# max7219.net
KiCad netlist of a schematic drawn in EAGLE
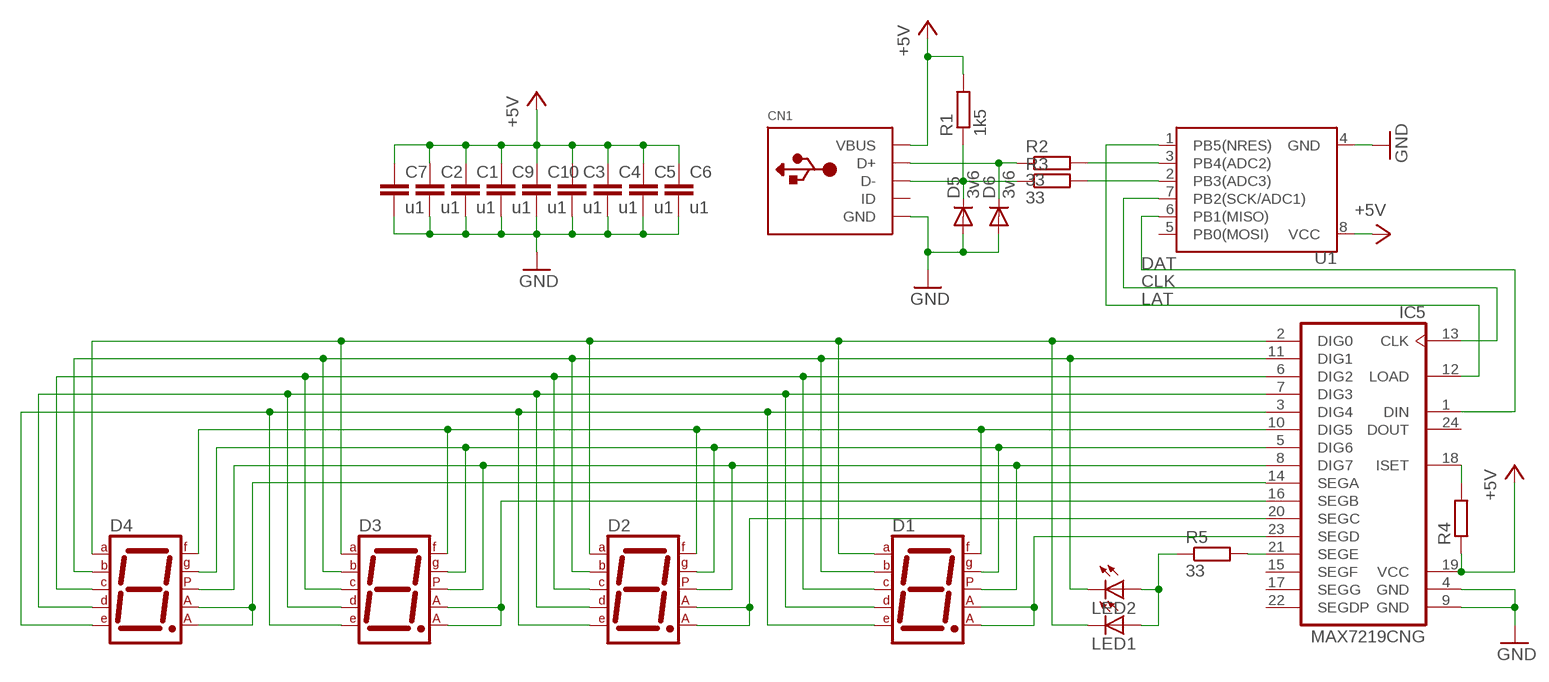
[diagram p0: schematic, sheet 1]

(export (version "E")
  (design (tool "Eeschema 10.0.6"))
  (components
    (comp (ref "C1")
      (value "u1")
      (footprint "eagle-import:C0805K")
      (libsource (lib "eagle-import") (part "C-EUC0805K"))
    )
    (comp (ref "C2")
      (value "u1")
      (footprint "eagle-import:C0805K")
      (libsource (lib "eagle-import") (part "C-EUC0805K"))
    )
    (comp (ref "C3")
      (value "u1")
      (footprint "eagle-import:C0805K")
      (libsource (lib "eagle-import") (part "C-EUC0805K"))
    )
    (comp (ref "C4")
      (value "u1")
      (footprint "eagle-import:C0805K")
      (libsource (lib "eagle-import") (part "C-EUC0805K"))
    )
    (comp (ref "C5")
      (value "u1")
      (footprint "eagle-import:C0805K")
      (libsource (lib "eagle-import") (part "C-EUC0805K"))
    )
    (comp (ref "C6")
      (value "u1")
      (footprint "eagle-import:C0805K")
      (libsource (lib "eagle-import") (part "C-EUC0805K"))
    )
    (comp (ref "C7")
      (value "u1")
      (footprint "eagle-import:C0805K")
      (libsource (lib "eagle-import") (part "C-EUC0805K"))
    )
    (comp (ref "C9")
      (value "u1")
      (footprint "eagle-import:C0805K")
      (libsource (lib "eagle-import") (part "C-EUC0805K"))
    )
    (comp (ref "C10")
      (value "u1")
      (footprint "eagle-import:C0805K")
      (libsource (lib "eagle-import") (part "C-EUC0805K"))
    )
    (comp (ref "CN1")
      (value "USBTHM")
      (footprint "eagle-import:USB-MINIB-THM")
      (libsource (lib "eagle-import") (part "USBTHM"))
    )
    (comp (ref "D1")
      (value "7SEG-CA")
      (footprint "eagle-import:7SEG-13")
      (libsource (lib "eagle-import") (part "7SEG-CA"))
    )
    (comp (ref "D2")
      (value "7SEG-CA")
      (footprint "eagle-import:7SEG-13")
      (libsource (lib "eagle-import") (part "7SEG-CA"))
    )
    (comp (ref "D3")
      (value "7SEG-CA")
      (footprint "eagle-import:7SEG-13")
      (libsource (lib "eagle-import") (part "7SEG-CA"))
    )
    (comp (ref "D4")
      (value "7SEG-CA")
      (footprint "eagle-import:7SEG-13")
      (libsource (lib "eagle-import") (part "7SEG-CA"))
    )
    (comp (ref "D5")
      (value "3v6")
      (footprint "eagle-import:MINIMELF")
      (libsource (lib "eagle-import") (part "DIODE-MINIMELF"))
    )
    (comp (ref "D6")
      (value "3v6")
      (footprint "eagle-import:MINIMELF")
      (libsource (lib "eagle-import") (part "DIODE-MINIMELF"))
    )
    (comp (ref "IC5")
      (value "MAX7219CNG")
      (footprint "eagle-import:DIL24-3")
      (fields (field (name "MF") "MAXIM"))
      (libsource (lib "eagle-import") (part "MAX7219CNG"))
    )
    (comp (ref "LED1")
      (value "LED3MM")
      (footprint "eagle-import:LED3MM")
      (libsource (lib "eagle-import") (part "LED3MM"))
    )
    (comp (ref "LED2")
      (value "LED3MM")
      (footprint "eagle-import:LED3MM")
      (libsource (lib "eagle-import") (part "LED3MM"))
    )
    (comp (ref "R1")
      (value "1k5")
      (footprint "eagle-import:M0805")
      (libsource (lib "eagle-import") (part "R-EU_M0805"))
    )
    (comp (ref "R2")
      (value "33")
      (footprint "eagle-import:M0805")
      (libsource (lib "eagle-import") (part "R-EU_M0805"))
    )
    (comp (ref "R3")
      (value "33")
      (footprint "eagle-import:M0805")
      (libsource (lib "eagle-import") (part "R-EU_M0805"))
    )
    (comp (ref "R4")
      (value "R-EU_R0805")
      (footprint "eagle-import:R0805")
      (libsource (lib "eagle-import") (part "R-EU_R0805"))
    )
    (comp (ref "R5")
      (value "33")
      (footprint "eagle-import:M0805")
      (libsource (lib "eagle-import") (part "R-EU_M0805"))
    )
    (comp (ref "U1")
      (value "ATTINY45ATTINYX5-20-DIP-GAP")
      (footprint "eagle-import:DIL08")
      (libsource (lib "eagle-import") (part "ATTINY45ATTINYX5-20-DIP-GAP"))
    )
  )
  (nets
    (net (code "1") (name "+5V") (class "Default")
      (node (ref "C1") (pin "1") (pinfunction "1_1") (pintype "passive"))
      (node (ref "C10") (pin "1") (pinfunction "1_1") (pintype "passive"))
      (node (ref "C2") (pin "1") (pinfunction "1_1") (pintype "passive"))
      (node (ref "C3") (pin "1") (pinfunction "1_1") (pintype "passive"))
      (node (ref "C4") (pin "1") (pinfunction "1_1") (pintype "passive"))
      (node (ref "C5") (pin "1") (pinfunction "1_1") (pintype "passive"))
      (node (ref "C6") (pin "1") (pinfunction "1_1") (pintype "passive"))
      (node (ref "C7") (pin "1") (pinfunction "1_1") (pintype "passive"))
      (node (ref "C9") (pin "1") (pinfunction "1_1") (pintype "passive"))
      (node (ref "CN1") (pin "VBUS") (pinfunction "VBUS_VBUS") (pintype "power_in"))
      (node (ref "IC5") (pin "19") (pinfunction "VCC_19") (pintype "power_in"))
      (node (ref "R1") (pin "2") (pinfunction "2_2") (pintype "passive"))
      (node (ref "R4") (pin "1") (pinfunction "1_1") (pintype "passive"))
      (node (ref "U1") (pin "8") (pinfunction "VCC_8") (pintype "bidirectional"))
    )
    (net (code "2") (name "/CLK") (class "Default")
      (node (ref "IC5") (pin "13") (pinfunction "CLK_13") (pintype "input"))
      (node (ref "U1") (pin "7") (pinfunction "PB2(SCK/ADC1)_7") (pintype "bidirectional"))
    )
    (net (code "3") (name "/DAT") (class "Default")
      (node (ref "IC5") (pin "1") (pinfunction "DIN_1") (pintype "input"))
      (node (ref "U1") (pin "6") (pinfunction "PB1(MISO)_6") (pintype "bidirectional"))
    )
    (net (code "4") (name "/LAT") (class "Default")
      (node (ref "IC5") (pin "12") (pinfunction "LOAD_12") (pintype "input"))
      (node (ref "U1") (pin "1") (pinfunction "PB5(NRES)_1") (pintype "bidirectional"))
    )
    (net (code "5") (name "GND") (class "Default")
      (node (ref "C1") (pin "2") (pinfunction "2_2") (pintype "passive"))
      (node (ref "C10") (pin "2") (pinfunction "2_2") (pintype "passive"))
      (node (ref "C2") (pin "2") (pinfunction "2_2") (pintype "passive"))
      (node (ref "C3") (pin "2") (pinfunction "2_2") (pintype "passive"))
      (node (ref "C4") (pin "2") (pinfunction "2_2") (pintype "passive"))
      (node (ref "C5") (pin "2") (pinfunction "2_2") (pintype "passive"))
      (node (ref "C6") (pin "2") (pinfunction "2_2") (pintype "passive"))
      (node (ref "C7") (pin "2") (pinfunction "2_2") (pintype "passive"))
      (node (ref "C9") (pin "2") (pinfunction "2_2") (pintype "passive"))
      (node (ref "CN1") (pin "GND") (pinfunction "GND_GND") (pintype "power_in"))
      (node (ref "D5") (pin "A") (pinfunction "A_A") (pintype "passive"))
      (node (ref "D6") (pin "A") (pinfunction "A_A") (pintype "passive"))
      (node (ref "IC5") (pin "4") (pinfunction "GND_4") (pintype "power_in"))
      (node (ref "IC5") (pin "9") (pinfunction "GND_9") (pintype "power_in"))
      (node (ref "U1") (pin "4") (pinfunction "GND_4") (pintype "bidirectional"))
    )
    (net (code "6") (name "Net-(CN1-PadD+)") (class "Default")
      (node (ref "CN1") (pin "D+") (pinfunction "D+_D+") (pintype "bidirectional"))
      (node (ref "D6") (pin "C") (pinfunction "C_C") (pintype "passive"))
      (node (ref "R2") (pin "1") (pinfunction "1_1") (pintype "passive"))
    )
    (net (code "7") (name "Net-(CN1-PadD-)") (class "Default")
      (node (ref "CN1") (pin "D-") (pinfunction "D-_D-") (pintype "bidirectional"))
      (node (ref "D5") (pin "C") (pinfunction "C_C") (pintype "passive"))
      (node (ref "R1") (pin "1") (pinfunction "1_1") (pintype "passive"))
      (node (ref "R3") (pin "1") (pinfunction "1_1") (pintype "passive"))
    )
    (net (code "8") (name "Net-(D1-A)") (class "Default")
      (node (ref "D1") (pin "7") (pinfunction "A_7") (pintype "passive"))
      (node (ref "D2") (pin "7") (pinfunction "A_7") (pintype "passive"))
      (node (ref "D3") (pin "7") (pinfunction "A_7") (pintype "passive"))
      (node (ref "D4") (pin "7") (pinfunction "A_7") (pintype "passive"))
      (node (ref "IC5") (pin "2") (pinfunction "DIG0_2") (pintype "output"))
      (node (ref "LED1") (pin "K") (pinfunction "C_K") (pintype "passive"))
    )
    (net (code "9") (name "Net-(D1-B)") (class "Default")
      (node (ref "D1") (pin "6") (pinfunction "B_6") (pintype "passive"))
      (node (ref "D2") (pin "6") (pinfunction "B_6") (pintype "passive"))
      (node (ref "D3") (pin "6") (pinfunction "B_6") (pintype "passive"))
      (node (ref "D4") (pin "6") (pinfunction "B_6") (pintype "passive"))
      (node (ref "IC5") (pin "11") (pinfunction "DIG1_11") (pintype "output"))
      (node (ref "LED2") (pin "K") (pinfunction "C_K") (pintype "passive"))
    )
    (net (code "10") (name "Net-(D1-C)") (class "Default")
      (node (ref "D1") (pin "4") (pinfunction "C_4") (pintype "passive"))
      (node (ref "D2") (pin "4") (pinfunction "C_4") (pintype "passive"))
      (node (ref "D3") (pin "4") (pinfunction "C_4") (pintype "passive"))
      (node (ref "D4") (pin "4") (pinfunction "C_4") (pintype "passive"))
      (node (ref "IC5") (pin "6") (pinfunction "DIG2_6") (pintype "output"))
    )
    (net (code "11") (name "Net-(D1-CA1)") (class "Default")
      (node (ref "D1") (pin "3") (pinfunction "CA1_3") (pintype "passive"))
      (node (ref "D1") (pin "8") (pinfunction "CA2_8") (pintype "passive"))
      (node (ref "IC5") (pin "23") (pinfunction "SEGD_23") (pintype "output"))
    )
    (net (code "12") (name "Net-(D1-D)") (class "Default")
      (node (ref "D1") (pin "2") (pinfunction "D_2") (pintype "passive"))
      (node (ref "D2") (pin "2") (pinfunction "D_2") (pintype "passive"))
      (node (ref "D3") (pin "2") (pinfunction "D_2") (pintype "passive"))
      (node (ref "D4") (pin "2") (pinfunction "D_2") (pintype "passive"))
      (node (ref "IC5") (pin "7") (pinfunction "DIG3_7") (pintype "output"))
    )
    (net (code "13") (name "Net-(D1-DP)") (class "Default")
      (node (ref "D1") (pin "5") (pinfunction "DP_5") (pintype "passive"))
      (node (ref "D2") (pin "5") (pinfunction "DP_5") (pintype "passive"))
      (node (ref "D3") (pin "5") (pinfunction "DP_5") (pintype "passive"))
      (node (ref "D4") (pin "5") (pinfunction "DP_5") (pintype "passive"))
      (node (ref "IC5") (pin "8") (pinfunction "DIG7_8") (pintype "output"))
    )
    (net (code "14") (name "Net-(D1-E)") (class "Default")
      (node (ref "D1") (pin "1") (pinfunction "E_1") (pintype "passive"))
      (node (ref "D2") (pin "1") (pinfunction "E_1") (pintype "passive"))
      (node (ref "D3") (pin "1") (pinfunction "E_1") (pintype "passive"))
      (node (ref "D4") (pin "1") (pinfunction "E_1") (pintype "passive"))
      (node (ref "IC5") (pin "3") (pinfunction "DIG4_3") (pintype "output"))
    )
    (net (code "15") (name "Net-(D1-F)") (class "Default")
      (node (ref "D1") (pin "9") (pinfunction "F_9") (pintype "passive"))
      (node (ref "D2") (pin "9") (pinfunction "F_9") (pintype "passive"))
      (node (ref "D3") (pin "9") (pinfunction "F_9") (pintype "passive"))
      (node (ref "D4") (pin "9") (pinfunction "F_9") (pintype "passive"))
      (node (ref "IC5") (pin "10") (pinfunction "DIG5_10") (pintype "output"))
    )
    (net (code "16") (name "Net-(D1-G)") (class "Default")
      (node (ref "D1") (pin "10") (pinfunction "G_10") (pintype "passive"))
      (node (ref "D2") (pin "10") (pinfunction "G_10") (pintype "passive"))
      (node (ref "D3") (pin "10") (pinfunction "G_10") (pintype "passive"))
      (node (ref "D4") (pin "10") (pinfunction "G_10") (pintype "passive"))
      (node (ref "IC5") (pin "5") (pinfunction "DIG6_5") (pintype "output"))
    )
    (net (code "17") (name "Net-(D2-CA1)") (class "Default")
      (node (ref "D2") (pin "3") (pinfunction "CA1_3") (pintype "passive"))
      (node (ref "D2") (pin "8") (pinfunction "CA2_8") (pintype "passive"))
      (node (ref "IC5") (pin "20") (pinfunction "SEGC_20") (pintype "output"))
    )
    (net (code "18") (name "Net-(D3-CA1)") (class "Default")
      (node (ref "D3") (pin "3") (pinfunction "CA1_3") (pintype "passive"))
      (node (ref "D3") (pin "8") (pinfunction "CA2_8") (pintype "passive"))
      (node (ref "IC5") (pin "16") (pinfunction "SEGB_16") (pintype "output"))
    )
    (net (code "19") (name "Net-(D4-CA1)") (class "Default")
      (node (ref "D4") (pin "3") (pinfunction "CA1_3") (pintype "passive"))
      (node (ref "D4") (pin "8") (pinfunction "CA2_8") (pintype "passive"))
      (node (ref "IC5") (pin "14") (pinfunction "SEGA_14") (pintype "output"))
    )
    (net (code "20") (name "Net-(IC5-ISET)") (class "Default")
      (node (ref "IC5") (pin "18") (pinfunction "ISET_18") (pintype "input"))
      (node (ref "R4") (pin "2") (pinfunction "2_2") (pintype "passive"))
    )
    (net (code "21") (name "Net-(IC5-SEGE)") (class "Default")
      (node (ref "IC5") (pin "21") (pinfunction "SEGE_21") (pintype "output"))
      (node (ref "R5") (pin "2") (pinfunction "2_2") (pintype "passive"))
    )
    (net (code "22") (name "Net-(LED1-PadA)") (class "Default")
      (node (ref "LED1") (pin "A") (pinfunction "A_A") (pintype "passive"))
      (node (ref "LED2") (pin "A") (pinfunction "A_A") (pintype "passive"))
      (node (ref "R5") (pin "1") (pinfunction "1_1") (pintype "passive"))
    )
    (net (code "23") (name "Net-(U1-PB3(ADC3))") (class "Default")
      (node (ref "R3") (pin "2") (pinfunction "2_2") (pintype "passive"))
      (node (ref "U1") (pin "2") (pinfunction "PB3(ADC3)_2") (pintype "bidirectional"))
    )
    (net (code "24") (name "Net-(U1-PB4(ADC2))") (class "Default")
      (node (ref "R2") (pin "2") (pinfunction "2_2") (pintype "passive"))
      (node (ref "U1") (pin "3") (pinfunction "PB4(ADC2)_3") (pintype "bidirectional"))
    )
    (net (code "25") (name "unconnected-(CN1-PadID)") (class "Default")
      (node (ref "CN1") (pin "ID") (pinfunction "ID_ID") (pintype "bidirectional"))
    )
    (net (code "26") (name "unconnected-(IC5-DOUT-Pad24)") (class "Default")
      (node (ref "IC5") (pin "24") (pinfunction "DOUT_24") (pintype "output"))
    )
    (net (code "27") (name "unconnected-(IC5-SEGDP-Pad22)") (class "Default")
      (node (ref "IC5") (pin "22") (pinfunction "SEGDP_22") (pintype "output"))
    )
    (net (code "28") (name "unconnected-(IC5-SEGF-Pad15)") (class "Default")
      (node (ref "IC5") (pin "15") (pinfunction "SEGF_15") (pintype "output"))
    )
    (net (code "29") (name "unconnected-(IC5-SEGG-Pad17)") (class "Default")
      (node (ref "IC5") (pin "17") (pinfunction "SEGG_17") (pintype "output"))
    )
    (net (code "30") (name "unconnected-(U1-PB0(MOSI)-Pad5)") (class "Default")
      (node (ref "U1") (pin "5") (pinfunction "PB0(MOSI)_5") (pintype "bidirectional"))
    )
  )
)
